# voltage_quadrupler.net
KiCad netlist of a schematic drawn in EAGLE
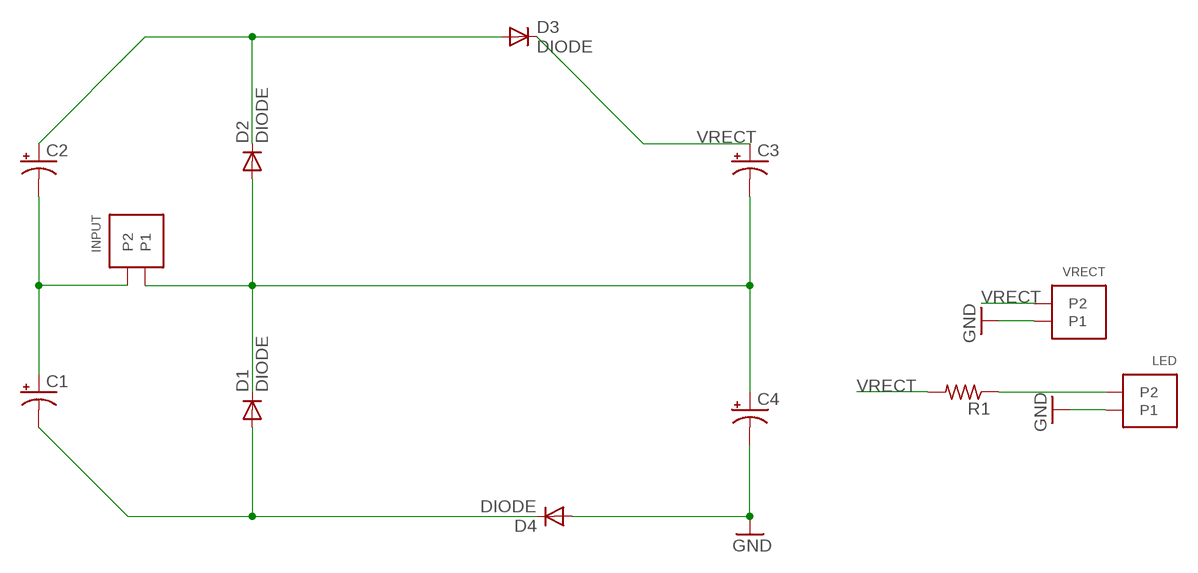
[diagram p0: schematic, sheet 1]

(export (version "E")
  (design (tool "Eeschema 10.0.6"))
  (components
    (comp (ref "C1")
      (value "CPOL-USE7.5-18")
      (footprint "eagle-import:E7,5-18")
      (libsource (lib "eagle-import") (part "CPOL-USE7.5-18"))
    )
    (comp (ref "C2")
      (value "CPOL-USE7.5-18")
      (footprint "eagle-import:E7,5-18")
      (libsource (lib "eagle-import") (part "CPOL-USE7.5-18"))
    )
    (comp (ref "C3")
      (value "CPOL-USE7.5-18")
      (footprint "eagle-import:E7,5-18")
      (libsource (lib "eagle-import") (part "CPOL-USE7.5-18"))
    )
    (comp (ref "C4")
      (value "CPOL-USE7.5-18")
      (footprint "eagle-import:E7,5-18")
      (libsource (lib "eagle-import") (part "CPOL-USE7.5-18"))
    )
    (comp (ref "D1")
      (value "DIODE")
      (footprint "eagle-import:DO-214AB")
      (libsource (lib "eagle-import") (part "DIODE"))
    )
    (comp (ref "D2")
      (value "DIODE")
      (footprint "eagle-import:DO-214AB")
      (libsource (lib "eagle-import") (part "DIODE"))
    )
    (comp (ref "D3")
      (value "DIODE")
      (footprint "eagle-import:DO-214AB")
      (libsource (lib "eagle-import") (part "DIODE"))
    )
    (comp (ref "D4")
      (value "DIODE")
      (footprint "eagle-import:DO-214AB")
      (libsource (lib "eagle-import") (part "DIODE"))
    )
    (comp (ref "INPUT")
      (value "DF3-2")
      (footprint "eagle-import:DF3-2")
      (libsource (lib "eagle-import") (part "DF3-2"))
    )
    (comp (ref "LED")
      (value "DF3-2")
      (footprint "eagle-import:DF3-2")
      (libsource (lib "eagle-import") (part "DF3-2"))
    )
    (comp (ref "R1")
      (value "R-US_0207/7")
      (footprint "eagle-import:0207_7")
      (libsource (lib "eagle-import") (part "R-US_0207/7"))
    )
    (comp (ref "VRECT")
      (value "DF3-2")
      (footprint "eagle-import:DF3-2")
      (libsource (lib "eagle-import") (part "DF3-2"))
    )
  )
  (nets
    (net (code "1") (name "/VRECT") (class "Default")
      (node (ref "C3") (pin "+") (pinfunction "+_+") (pintype "passive"))
      (node (ref "D3") (pin "P$1") (pinfunction "C_P$1") (pintype "passive"))
      (node (ref "R1") (pin "2") (pinfunction "2_2") (pintype "passive"))
      (node (ref "VRECT") (pin "P$2") (pinfunction "P2_P$2") (pintype "bidirectional"))
    )
    (net (code "2") (name "GND") (class "Default")
      (node (ref "C4") (pin "-") (pinfunction "-_-") (pintype "passive"))
      (node (ref "D4") (pin "P$2") (pinfunction "A_P$2") (pintype "passive"))
      (node (ref "LED") (pin "P$1") (pinfunction "P1_P$1") (pintype "bidirectional"))
      (node (ref "VRECT") (pin "P$1") (pinfunction "P1_P$1") (pintype "bidirectional"))
    )
    (net (code "3") (name "Net-(D1-A)") (class "Default")
      (node (ref "C1") (pin "-") (pinfunction "-_-") (pintype "passive"))
      (node (ref "D1") (pin "P$2") (pinfunction "A_P$2") (pintype "passive"))
      (node (ref "D4") (pin "P$1") (pinfunction "C_P$1") (pintype "passive"))
    )
    (net (code "4") (name "Net-(D1-C)") (class "Default")
      (node (ref "C3") (pin "-") (pinfunction "-_-") (pintype "passive"))
      (node (ref "C4") (pin "+") (pinfunction "+_+") (pintype "passive"))
      (node (ref "D1") (pin "P$1") (pinfunction "C_P$1") (pintype "passive"))
      (node (ref "D2") (pin "P$2") (pinfunction "A_P$2") (pintype "passive"))
      (node (ref "INPUT") (pin "P$1") (pinfunction "P1_P$1") (pintype "bidirectional"))
    )
    (net (code "5") (name "Net-(D2-C)") (class "Default")
      (node (ref "C2") (pin "+") (pinfunction "+_+") (pintype "passive"))
      (node (ref "D2") (pin "P$1") (pinfunction "C_P$1") (pintype "passive"))
      (node (ref "D3") (pin "P$2") (pinfunction "A_P$2") (pintype "passive"))
    )
    (net (code "6") (name "Net-(INPUT-P2)") (class "Default")
      (node (ref "C1") (pin "+") (pinfunction "+_+") (pintype "passive"))
      (node (ref "C2") (pin "-") (pinfunction "-_-") (pintype "passive"))
      (node (ref "INPUT") (pin "P$2") (pinfunction "P2_P$2") (pintype "bidirectional"))
    )
    (net (code "7") (name "Net-(LED-P2)") (class "Default")
      (node (ref "LED") (pin "P$2") (pinfunction "P2_P$2") (pintype "bidirectional"))
      (node (ref "R1") (pin "1") (pinfunction "1_1") (pintype "passive"))
    )
  )
)
